# modEEGamp_v1_1_-_Single.net
KiCad netlist of a schematic drawn in EAGLE
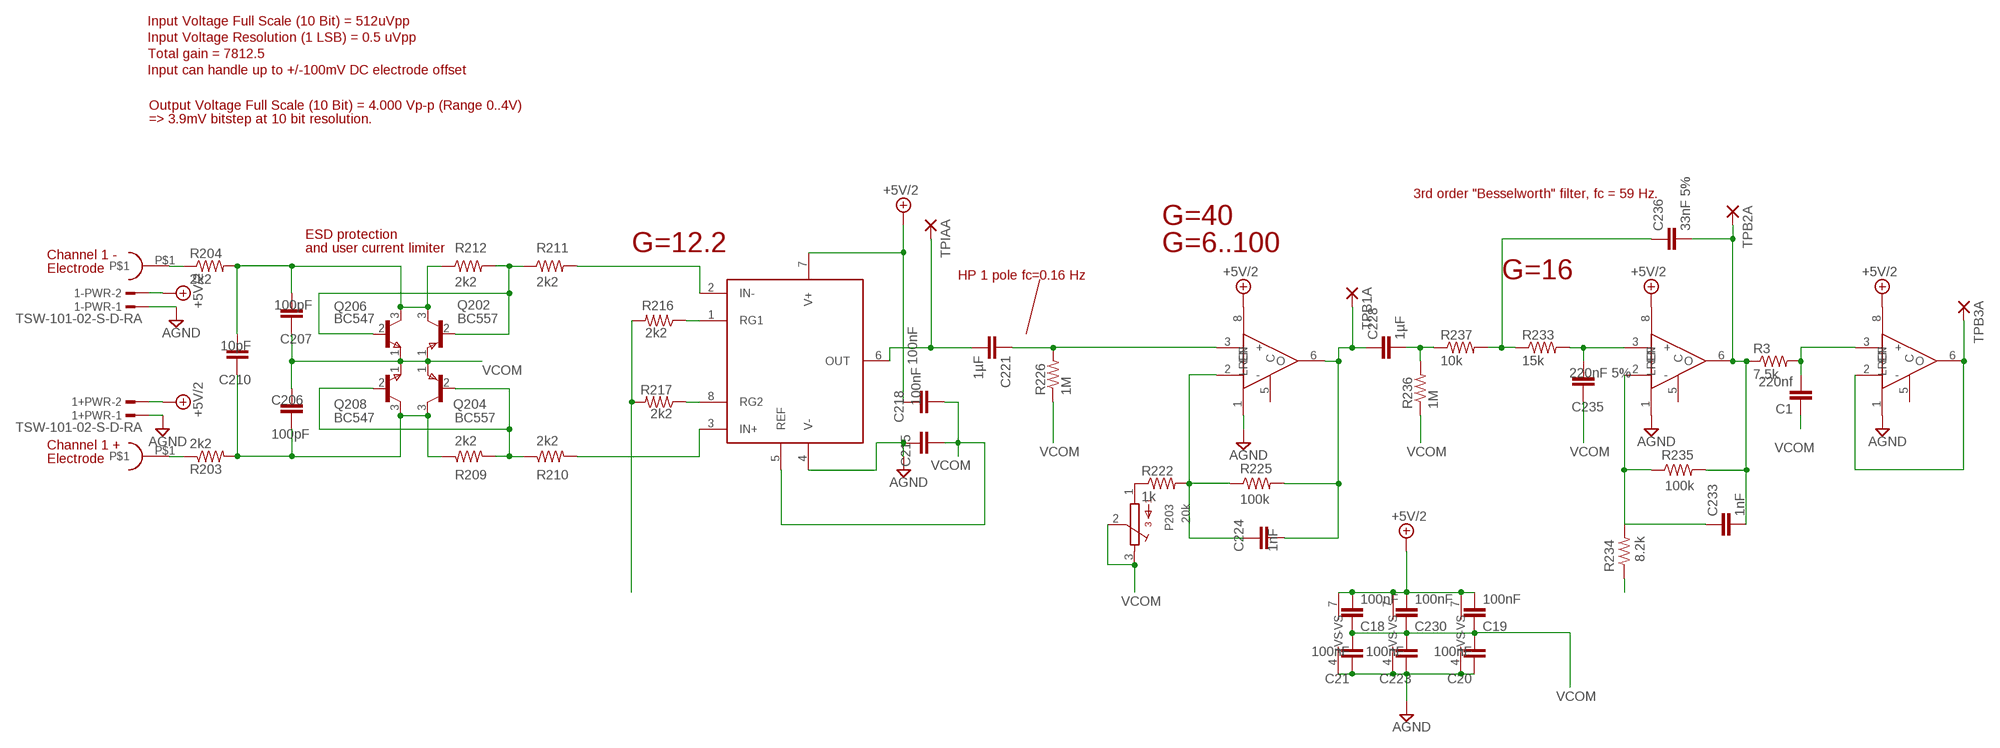
[diagram p0: schematic, sheet 1]

(export (version "E")
  (design (tool "Eeschema 10.0.6"))
  (components
    (comp (ref "1+PWR")
      (value "TSW-101-02-S-D-RA")
      (footprint "eagle-import:TSW-101-02-S-D-RA")
      (libsource (lib "eagle-import") (part "TSW-101-02-S-D-RA"))
    )
    (comp (ref "1-PWR")
      (value "TSW-101-02-S-D-RA")
      (footprint "eagle-import:TSW-101-02-S-D-RA")
      (libsource (lib "eagle-import") (part "TSW-101-02-S-D-RA"))
    )
    (comp (ref "C1")
      (value "220nf")
      (footprint "eagle-import:C1206")
      (libsource (lib "eagle-import") (part "C-EUC1206"))
    )
    (comp (ref "C1+")
      (value "DIN42802")
      (footprint "eagle-import:DIN42802")
      (libsource (lib "eagle-import") (part "DIN42802"))
    )
    (comp (ref "C1-")
      (value "DIN42802")
      (footprint "eagle-import:DIN42802")
      (libsource (lib "eagle-import") (part "DIN42802"))
    )
    (comp (ref "C18")
      (value "100nF")
      (footprint "eagle-import:C1206")
      (libsource (lib "eagle-import") (part "C-EUC1206"))
    )
    (comp (ref "C19")
      (value "100nF")
      (footprint "eagle-import:C1206")
      (libsource (lib "eagle-import") (part "C-EUC1206"))
    )
    (comp (ref "C20")
      (value "100nF")
      (footprint "eagle-import:C1206")
      (libsource (lib "eagle-import") (part "C-EUC1206"))
    )
    (comp (ref "C21")
      (value "100nF")
      (footprint "eagle-import:C1206")
      (libsource (lib "eagle-import") (part "C-EUC1206"))
    )
    (comp (ref "C206")
      (value "100pF")
      (footprint "eagle-import:C1206")
      (libsource (lib "eagle-import") (part "C-EUC1206"))
    )
    (comp (ref "C207")
      (value "100pF")
      (footprint "eagle-import:C1206")
      (libsource (lib "eagle-import") (part "C-EUC1206"))
    )
    (comp (ref "C210")
      (value "10pF")
      (footprint "eagle-import:C1206")
      (libsource (lib "eagle-import") (part "C-EUC1206"))
    )
    (comp (ref "C215")
      (value "100nF")
      (footprint "eagle-import:C1206")
      (libsource (lib "eagle-import") (part "C-EUC1206"))
    )
    (comp (ref "C218")
      (value "100nF")
      (footprint "eagle-import:C1206")
      (libsource (lib "eagle-import") (part "C-EUC1206"))
    )
    (comp (ref "C221")
      (value "1µF")
      (footprint "eagle-import:C050-024X044")
      (libsource (lib "eagle-import") (part "C-EU050-024X044"))
    )
    (comp (ref "C223")
      (value "100nF")
      (footprint "eagle-import:C1206")
      (libsource (lib "eagle-import") (part "C-EUC1206"))
    )
    (comp (ref "C224")
      (value "1nF")
      (footprint "eagle-import:C1206")
      (libsource (lib "eagle-import") (part "C-EUC1206"))
    )
    (comp (ref "C228")
      (value "1µF")
      (footprint "eagle-import:C050-024X044")
      (libsource (lib "eagle-import") (part "C-EU050-024X044"))
    )
    (comp (ref "C230")
      (value "100nF")
      (footprint "eagle-import:C1206")
      (libsource (lib "eagle-import") (part "C-EUC1206"))
    )
    (comp (ref "C233")
      (value "1nF")
      (footprint "eagle-import:C1206")
      (libsource (lib "eagle-import") (part "C-EUC1206"))
    )
    (comp (ref "C235")
      (value "220nF 5%")
      (footprint "eagle-import:C1206")
      (libsource (lib "eagle-import") (part "C-EUC1206"))
    )
    (comp (ref "C236")
      (value "33nF 5%")
      (footprint "eagle-import:C1206")
      (libsource (lib "eagle-import") (part "C-EUC1206"))
    )
    (comp (ref "P203")
      (value "20k")
      (footprint "eagle-import:S64Y")
      (libsource (lib "eagle-import") (part "S64Y"))
    )
    (comp (ref "Q202")
      (value "BC557")
      (footprint "eagle-import:TO92")
      (libsource (lib "eagle-import") (part "BC557"))
    )
    (comp (ref "Q204")
      (value "BC557")
      (footprint "eagle-import:TO92")
      (libsource (lib "eagle-import") (part "BC557"))
    )
    (comp (ref "Q206")
      (value "BC547")
      (footprint "eagle-import:TO92")
      (libsource (lib "eagle-import") (part "BC547"))
    )
    (comp (ref "Q208")
      (value "BC547")
      (footprint "eagle-import:TO92")
      (libsource (lib "eagle-import") (part "BC547"))
    )
    (comp (ref "R3")
      (value "7.5k")
      (footprint "eagle-import:R1206")
      (libsource (lib "eagle-import") (part "R-US_R1206"))
    )
    (comp (ref "R203")
      (value "2k2")
      (footprint "eagle-import:R1206")
      (libsource (lib "eagle-import") (part "R-US_R1206"))
    )
    (comp (ref "R204")
      (value "2k2")
      (footprint "eagle-import:R1206")
      (libsource (lib "eagle-import") (part "R-US_R1206"))
    )
    (comp (ref "R209")
      (value "2k2")
      (footprint "eagle-import:R1206")
      (libsource (lib "eagle-import") (part "R-US_R1206"))
    )
    (comp (ref "R210")
      (value "2k2")
      (footprint "eagle-import:R1206")
      (libsource (lib "eagle-import") (part "R-US_R1206"))
    )
    (comp (ref "R211")
      (value "2k2")
      (footprint "eagle-import:R1206")
      (libsource (lib "eagle-import") (part "R-US_R1206"))
    )
    (comp (ref "R212")
      (value "2k2")
      (footprint "eagle-import:R1206")
      (libsource (lib "eagle-import") (part "R-US_R1206"))
    )
    (comp (ref "R216")
      (value "2k2")
      (footprint "eagle-import:R1206")
      (libsource (lib "eagle-import") (part "R-US_R1206"))
    )
    (comp (ref "R217")
      (value "2k2")
      (footprint "eagle-import:R1206")
      (libsource (lib "eagle-import") (part "R-US_R1206"))
    )
    (comp (ref "R222")
      (value "1k")
      (footprint "eagle-import:R1206")
      (libsource (lib "eagle-import") (part "R-US_R1206"))
    )
    (comp (ref "R225")
      (value "100k")
      (footprint "eagle-import:R1206")
      (libsource (lib "eagle-import") (part "R-US_R1206"))
    )
    (comp (ref "R226")
      (value "1M")
      (footprint "eagle-import:R1206")
      (libsource (lib "eagle-import") (part "R-US_R1206"))
    )
    (comp (ref "R233")
      (value "15k")
      (footprint "eagle-import:R1206")
      (libsource (lib "eagle-import") (part "R-US_R1206"))
    )
    (comp (ref "R234")
      (value "8.2k")
      (footprint "eagle-import:R1206")
      (libsource (lib "eagle-import") (part "R-US_R1206"))
    )
    (comp (ref "R235")
      (value "100k")
      (footprint "eagle-import:R1206")
      (libsource (lib "eagle-import") (part "R-US_R1206"))
    )
    (comp (ref "R236")
      (value "1M")
      (footprint "eagle-import:R1206")
      (libsource (lib "eagle-import") (part "R-US_R1206"))
    )
    (comp (ref "R237")
      (value "10k")
      (footprint "eagle-import:R1206")
      (libsource (lib "eagle-import") (part "R-US_R1206"))
    )
    (comp (ref "TPB1A")
      (value "1,6/0,8")
      (footprint "eagle-import:1,6_0,8")
      (libsource (lib "eagle-import") (part "1,6/0,8"))
    )
    (comp (ref "TPB2A")
      (value "1,6/0,8")
      (footprint "eagle-import:1,6_0,8")
      (libsource (lib "eagle-import") (part "1,6/0,8"))
    )
    (comp (ref "TPB3A")
      (value "1,6/0,8")
      (footprint "eagle-import:1,6_0,8")
      (libsource (lib "eagle-import") (part "1,6/0,8"))
    )
    (comp (ref "TPIAA")
      (value "1,6/0,8")
      (footprint "eagle-import:1,6_0,8")
      (libsource (lib "eagle-import") (part "1,6/0,8"))
    )
    (comp (ref "U$1")
      (value "INA217")
      (footprint "eagle-import:DIL-08")
      (libsource (lib "eagle-import") (part "INA217"))
    )
    (comp (ref "U$2")
      (value "AD8021")
      (footprint "eagle-import:SOIC8")
      (libsource (lib "eagle-import") (part "AD8021"))
    )
    (comp (ref "U$3")
      (value "AD8021")
      (footprint "eagle-import:SOIC8")
      (libsource (lib "eagle-import") (part "AD8021"))
    )
    (comp (ref "U$16")
      (value "AD8021")
      (footprint "eagle-import:SOIC8")
      (libsource (lib "eagle-import") (part "AD8021"))
    )
  )
  (nets
    (net (code "1") (name "+5V{slash}2") (class "Default")
      (node (ref "1+PWR") (pin "2") (pinfunction "1_2") (pintype "passive"))
      (node (ref "1-PWR") (pin "2") (pinfunction "1_2") (pintype "passive"))
      (node (ref "C18") (pin "2") (pinfunction "2_2") (pintype "passive"))
      (node (ref "C19") (pin "2") (pinfunction "2_2") (pintype "passive"))
      (node (ref "C218") (pin "1") (pinfunction "1_1") (pintype "passive"))
      (node (ref "C230") (pin "2") (pinfunction "2_2") (pintype "passive"))
      (node (ref "U$1") (pin "7") (pinfunction "V+_7") (pintype "bidirectional"))
      (node (ref "U$16") (pin "7") (pinfunction "+VS_7") (pintype "bidirectional"))
      (node (ref "U$16") (pin "8") (pinfunction "EN_8") (pintype "bidirectional"))
      (node (ref "U$2") (pin "7") (pinfunction "+VS_7") (pintype "bidirectional"))
      (node (ref "U$2") (pin "8") (pinfunction "EN_8") (pintype "bidirectional"))
      (node (ref "U$3") (pin "7") (pinfunction "+VS_7") (pintype "bidirectional"))
      (node (ref "U$3") (pin "8") (pinfunction "EN_8") (pintype "bidirectional"))
    )
    (net (code "2") (name "/VCOM") (class "Default")
      (node (ref "C1") (pin "1") (pinfunction "1_1") (pintype "passive"))
      (node (ref "C18") (pin "1") (pinfunction "1_1") (pintype "passive"))
      (node (ref "C19") (pin "1") (pinfunction "1_1") (pintype "passive"))
      (node (ref "C20") (pin "2") (pinfunction "2_2") (pintype "passive"))
      (node (ref "C206") (pin "2") (pinfunction "2_2") (pintype "passive"))
      (node (ref "C207") (pin "1") (pinfunction "1_1") (pintype "passive"))
      (node (ref "C21") (pin "2") (pinfunction "2_2") (pintype "passive"))
      (node (ref "C215") (pin "2") (pinfunction "2_2") (pintype "passive"))
      (node (ref "C218") (pin "2") (pinfunction "2_2") (pintype "passive"))
      (node (ref "C223") (pin "2") (pinfunction "2_2") (pintype "passive"))
      (node (ref "C230") (pin "1") (pinfunction "1_1") (pintype "passive"))
      (node (ref "C235") (pin "1") (pinfunction "1_1") (pintype "passive"))
      (node (ref "P203") (pin "2") (pinfunction "2_2") (pintype "passive"))
      (node (ref "P203") (pin "3") (pinfunction "3_3") (pintype "passive"))
      (node (ref "Q202") (pin "1") (pinfunction "E_1") (pintype "passive"))
      (node (ref "Q204") (pin "1") (pinfunction "E_1") (pintype "passive"))
      (node (ref "Q206") (pin "1") (pinfunction "E_1") (pintype "passive"))
      (node (ref "Q208") (pin "1") (pinfunction "E_1") (pintype "passive"))
      (node (ref "R226") (pin "1") (pinfunction "1_1") (pintype "passive"))
      (node (ref "R234") (pin "1") (pinfunction "1_1") (pintype "passive"))
      (node (ref "R236") (pin "1") (pinfunction "1_1") (pintype "passive"))
      (node (ref "U$1") (pin "5") (pinfunction "REF_5") (pintype "bidirectional"))
    )
    (net (code "3") (name "AGND") (class "Default")
      (node (ref "1+PWR") (pin "1") (pinfunction "1_1") (pintype "passive"))
      (node (ref "1-PWR") (pin "1") (pinfunction "1_1") (pintype "passive"))
      (node (ref "C20") (pin "1") (pinfunction "1_1") (pintype "passive"))
      (node (ref "C21") (pin "1") (pinfunction "1_1") (pintype "passive"))
      (node (ref "C215") (pin "1") (pinfunction "1_1") (pintype "passive"))
      (node (ref "C223") (pin "1") (pinfunction "1_1") (pintype "passive"))
      (node (ref "U$1") (pin "4") (pinfunction "V-_4") (pintype "bidirectional"))
      (node (ref "U$16") (pin "1") (pinfunction "LREF_1") (pintype "bidirectional"))
      (node (ref "U$16") (pin "4") (pinfunction "-VS_4") (pintype "bidirectional"))
      (node (ref "U$2") (pin "1") (pinfunction "LREF_1") (pintype "bidirectional"))
      (node (ref "U$2") (pin "4") (pinfunction "-VS_4") (pintype "bidirectional"))
      (node (ref "U$3") (pin "1") (pinfunction "LREF_1") (pintype "bidirectional"))
      (node (ref "U$3") (pin "4") (pinfunction "-VS_4") (pintype "bidirectional"))
    )
    (net (code "4") (name "Net-(C1+-PadP$1)") (class "Default")
      (node (ref "C1+") (pin "P$1") (pinfunction "P$1_P$1") (pintype "bidirectional"))
      (node (ref "R203") (pin "1") (pinfunction "1_1") (pintype "passive"))
    )
    (net (code "5") (name "Net-(C1--PadP$1)") (class "Default")
      (node (ref "C1-") (pin "P$1") (pinfunction "P$1_P$1") (pintype "bidirectional"))
      (node (ref "R204") (pin "1") (pinfunction "1_1") (pintype "passive"))
    )
    (net (code "6") (name "Net-(C228-Pad2)") (class "Default")
      (node (ref "C228") (pin "2") (pinfunction "2_2") (pintype "passive"))
      (node (ref "R236") (pin "2") (pinfunction "2_2") (pintype "passive"))
      (node (ref "R237") (pin "1") (pinfunction "1_1") (pintype "passive"))
    )
    (net (code "7") (name "Net-(C236-Pad1)") (class "Default")
      (node (ref "C236") (pin "1") (pinfunction "1_1") (pintype "passive"))
      (node (ref "R233") (pin "1") (pinfunction "1_1") (pintype "passive"))
      (node (ref "R237") (pin "2") (pinfunction "2_2") (pintype "passive"))
    )
    (net (code "8") (name "Net-(P203-Pad1)") (class "Default")
      (node (ref "P203") (pin "1") (pinfunction "1_1") (pintype "passive"))
      (node (ref "R222") (pin "1") (pinfunction "1_1") (pintype "passive"))
    )
    (net (code "9") (name "Net-(Q202-B)") (class "Default")
      (node (ref "Q202") (pin "2") (pinfunction "B_2") (pintype "passive"))
      (node (ref "Q206") (pin "2") (pinfunction "B_2") (pintype "passive"))
      (node (ref "R211") (pin "1") (pinfunction "1_1") (pintype "passive"))
      (node (ref "R212") (pin "2") (pinfunction "2_2") (pintype "passive"))
    )
    (net (code "10") (name "Net-(Q202-C)") (class "Default")
      (node (ref "C207") (pin "2") (pinfunction "2_2") (pintype "passive"))
      (node (ref "C210") (pin "2") (pinfunction "2_2") (pintype "passive"))
      (node (ref "Q202") (pin "3") (pinfunction "C_3") (pintype "passive"))
      (node (ref "Q206") (pin "3") (pinfunction "C_3") (pintype "passive"))
      (node (ref "R204") (pin "2") (pinfunction "2_2") (pintype "passive"))
      (node (ref "R212") (pin "1") (pinfunction "1_1") (pintype "passive"))
    )
    (net (code "11") (name "Net-(Q204-B)") (class "Default")
      (node (ref "Q204") (pin "2") (pinfunction "B_2") (pintype "passive"))
      (node (ref "Q208") (pin "2") (pinfunction "B_2") (pintype "passive"))
      (node (ref "R209") (pin "2") (pinfunction "2_2") (pintype "passive"))
      (node (ref "R210") (pin "1") (pinfunction "1_1") (pintype "passive"))
    )
    (net (code "12") (name "Net-(Q204-C)") (class "Default")
      (node (ref "C206") (pin "1") (pinfunction "1_1") (pintype "passive"))
      (node (ref "C210") (pin "1") (pinfunction "1_1") (pintype "passive"))
      (node (ref "Q204") (pin "3") (pinfunction "C_3") (pintype "passive"))
      (node (ref "Q208") (pin "3") (pinfunction "C_3") (pintype "passive"))
      (node (ref "R203") (pin "2") (pinfunction "2_2") (pintype "passive"))
      (node (ref "R209") (pin "1") (pinfunction "1_1") (pintype "passive"))
    )
    (net (code "13") (name "Net-(R216-Pad2)") (class "Default")
      (node (ref "R216") (pin "2") (pinfunction "2_2") (pintype "passive"))
      (node (ref "R217") (pin "2") (pinfunction "2_2") (pintype "passive"))
    )
    (net (code "14") (name "Net-(TPB1A-P)") (class "Default")
      (node (ref "C224") (pin "2") (pinfunction "2_2") (pintype "passive"))
      (node (ref "C228") (pin "1") (pinfunction "1_1") (pintype "passive"))
      (node (ref "R225") (pin "2") (pinfunction "2_2") (pintype "passive"))
      (node (ref "TPB1A") (pin "1") (pinfunction "P_1") (pintype "passive"))
      (node (ref "U$2") (pin "6") (pinfunction "O_6") (pintype "bidirectional"))
    )
    (net (code "15") (name "Net-(TPB2A-P)") (class "Default")
      (node (ref "C233") (pin "2") (pinfunction "2_2") (pintype "passive"))
      (node (ref "C236") (pin "2") (pinfunction "2_2") (pintype "passive"))
      (node (ref "R235") (pin "2") (pinfunction "2_2") (pintype "passive"))
      (node (ref "R3") (pin "1") (pinfunction "1_1") (pintype "passive"))
      (node (ref "TPB2A") (pin "1") (pinfunction "P_1") (pintype "passive"))
      (node (ref "U$3") (pin "6") (pinfunction "O_6") (pintype "bidirectional"))
    )
    (net (code "16") (name "Net-(TPB3A-P)") (class "Default")
      (node (ref "TPB3A") (pin "1") (pinfunction "P_1") (pintype "passive"))
      (node (ref "U$16") (pin "2") (pinfunction "-_2") (pintype "bidirectional"))
      (node (ref "U$16") (pin "6") (pinfunction "O_6") (pintype "bidirectional"))
    )
    (net (code "17") (name "Net-(TPIAA-P)") (class "Default")
      (node (ref "C221") (pin "2") (pinfunction "2_2") (pintype "passive"))
      (node (ref "TPIAA") (pin "1") (pinfunction "P_1") (pintype "passive"))
      (node (ref "U$1") (pin "6") (pinfunction "OUT_6") (pintype "bidirectional"))
    )
    (net (code "18") (name "Net-(U$1-IN+)") (class "Default")
      (node (ref "R210") (pin "2") (pinfunction "2_2") (pintype "passive"))
      (node (ref "U$1") (pin "3") (pinfunction "IN+_3") (pintype "bidirectional"))
    )
    (net (code "19") (name "Net-(U$1-IN-)") (class "Default")
      (node (ref "R211") (pin "2") (pinfunction "2_2") (pintype "passive"))
      (node (ref "U$1") (pin "2") (pinfunction "IN-_2") (pintype "bidirectional"))
    )
    (net (code "20") (name "Net-(U$1-RG1)") (class "Default")
      (node (ref "R216") (pin "1") (pinfunction "1_1") (pintype "passive"))
      (node (ref "U$1") (pin "1") (pinfunction "RG1_1") (pintype "bidirectional"))
    )
    (net (code "21") (name "Net-(U$1-RG2)") (class "Default")
      (node (ref "R217") (pin "1") (pinfunction "1_1") (pintype "passive"))
      (node (ref "U$1") (pin "8") (pinfunction "RG2_8") (pintype "bidirectional"))
    )
    (net (code "22") (name "Net-(U$2A-+)") (class "Default")
      (node (ref "C221") (pin "1") (pinfunction "1_1") (pintype "passive"))
      (node (ref "R226") (pin "2") (pinfunction "2_2") (pintype "passive"))
      (node (ref "U$2") (pin "3") (pinfunction "+_3") (pintype "bidirectional"))
    )
    (net (code "23") (name "Net-(U$2A--)") (class "Default")
      (node (ref "C224") (pin "1") (pinfunction "1_1") (pintype "passive"))
      (node (ref "R222") (pin "2") (pinfunction "2_2") (pintype "passive"))
      (node (ref "R225") (pin "1") (pinfunction "1_1") (pintype "passive"))
      (node (ref "U$2") (pin "2") (pinfunction "-_2") (pintype "bidirectional"))
    )
    (net (code "24") (name "Net-(U$3A-+)") (class "Default")
      (node (ref "C235") (pin "2") (pinfunction "2_2") (pintype "passive"))
      (node (ref "R233") (pin "2") (pinfunction "2_2") (pintype "passive"))
      (node (ref "U$3") (pin "3") (pinfunction "+_3") (pintype "bidirectional"))
    )
    (net (code "25") (name "Net-(U$3A--)") (class "Default")
      (node (ref "C233") (pin "1") (pinfunction "1_1") (pintype "passive"))
      (node (ref "R234") (pin "2") (pinfunction "2_2") (pintype "passive"))
      (node (ref "R235") (pin "1") (pinfunction "1_1") (pintype "passive"))
      (node (ref "U$3") (pin "2") (pinfunction "-_2") (pintype "bidirectional"))
    )
    (net (code "26") (name "Net-(U$16A-+)") (class "Default")
      (node (ref "C1") (pin "2") (pinfunction "2_2") (pintype "passive"))
      (node (ref "R3") (pin "2") (pinfunction "2_2") (pintype "passive"))
      (node (ref "U$16") (pin "3") (pinfunction "+_3") (pintype "bidirectional"))
    )
    (net (code "27") (name "unconnected-(U$2A-C-Pad5)") (class "Default")
      (node (ref "U$2") (pin "5") (pinfunction "C_5") (pintype "bidirectional"))
    )
    (net (code "28") (name "unconnected-(U$3A-C-Pad5)") (class "Default")
      (node (ref "U$3") (pin "5") (pinfunction "C_5") (pintype "bidirectional"))
    )
    (net (code "29") (name "unconnected-(U$16A-C-Pad5)") (class "Default")
      (node (ref "U$16") (pin "5") (pinfunction "C_5") (pintype "bidirectional"))
    )
  )
)
